# Back_Drill_Example.net
KiCad netlist of a schematic drawn in Altium Designer
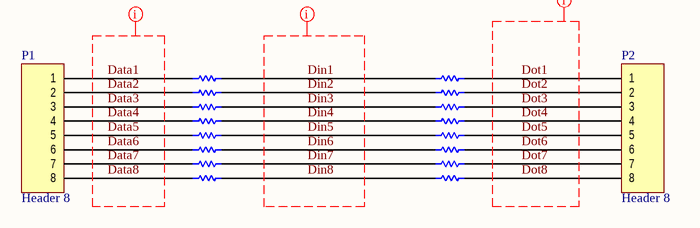
[diagram p0: Back Drill Example.SchDoc]

(export (version "E")
  (design (tool "Eeschema 10.0.6"))
  (components
    (comp (ref "P1")
      (value "Header 8")
      (footprint "HDR1X8")
      (description "Header, 8-Pin")
      (fields (field (name "PUBLISHER") "Altium Limited"))
      (libsource (lib "") (part "Header 8_1"))
    )
    (comp (ref "P2")
      (value "Header 8")
      (footprint "HDR1X8")
      (description "Header, 8-Pin")
      (fields (field (name "PUBLISHER") "Altium Limited"))
      (libsource (lib "Miscellaneous Connectors") (part "Header 8"))
    )
    (comp (ref "R1")
      (value "1K 0603")
      (footprint "0603_L")
      (fields
        (field (name "MANUFACTURER") "Panasonic Electronic Components")
        (field (name "MANUFACTURER PART NUMBER") "ERJ-3GEYJ102V")
        (field (name "TOLERANCE") "±5%")
      )
      (libsource (lib "WCTopping") (part "Res1K_0603"))
    )
    (comp (ref "R2")
      (value "1K 0603")
      (footprint "0603_L")
      (fields
        (field (name "MANUFACTURER") "Panasonic Electronic Components")
        (field (name "MANUFACTURER PART NUMBER") "ERJ-3GEYJ102V")
        (field (name "TOLERANCE") "±5%")
      )
      (libsource (lib "WCTopping") (part "Res1K_0603"))
    )
    (comp (ref "R3")
      (value "1K 0603")
      (footprint "0603_L")
      (fields
        (field (name "MANUFACTURER") "Panasonic Electronic Components")
        (field (name "MANUFACTURER PART NUMBER") "ERJ-3GEYJ102V")
        (field (name "TOLERANCE") "±5%")
      )
      (libsource (lib "WCTopping") (part "Res1K_0603"))
    )
    (comp (ref "R4")
      (value "1K 0603")
      (footprint "0603_L")
      (fields
        (field (name "MANUFACTURER") "Panasonic Electronic Components")
        (field (name "MANUFACTURER PART NUMBER") "ERJ-3GEYJ102V")
        (field (name "TOLERANCE") "±5%")
      )
      (libsource (lib "WCTopping") (part "Res1K_0603"))
    )
    (comp (ref "R5")
      (value "1K 0603")
      (footprint "0603_L")
      (fields
        (field (name "MANUFACTURER") "Panasonic Electronic Components")
        (field (name "MANUFACTURER PART NUMBER") "ERJ-3GEYJ102V")
        (field (name "TOLERANCE") "±5%")
      )
      (libsource (lib "WCTopping") (part "Res1K_0603"))
    )
    (comp (ref "R6")
      (value "1K 0603")
      (footprint "0603_L")
      (fields
        (field (name "MANUFACTURER") "Panasonic Electronic Components")
        (field (name "MANUFACTURER PART NUMBER") "ERJ-3GEYJ102V")
        (field (name "TOLERANCE") "±5%")
      )
      (libsource (lib "WCTopping") (part "Res1K_0603"))
    )
    (comp (ref "R7")
      (value "1K 0603")
      (footprint "0603_L")
      (fields
        (field (name "MANUFACTURER") "Panasonic Electronic Components")
        (field (name "MANUFACTURER PART NUMBER") "ERJ-3GEYJ102V")
        (field (name "TOLERANCE") "±5%")
      )
      (libsource (lib "WCTopping") (part "Res1K_0603"))
    )
    (comp (ref "R8")
      (value "1K 0603")
      (footprint "0603_L")
      (fields
        (field (name "MANUFACTURER") "Panasonic Electronic Components")
        (field (name "MANUFACTURER PART NUMBER") "ERJ-3GEYJ102V")
        (field (name "TOLERANCE") "±5%")
      )
      (libsource (lib "WCTopping") (part "Res1K_0603"))
    )
    (comp (ref "RS1")
      (value "1K 0603")
      (footprint "0603_L")
      (fields
        (field (name "MANUFACTURER") "Panasonic Electronic Components")
        (field (name "MANUFACTURER PART NUMBER") "ERJ-3GEYJ102V")
        (field (name "TOLERANCE") "±5%")
      )
      (libsource (lib "WCTopping") (part "Res1K_0603"))
    )
    (comp (ref "RS2")
      (value "1K 0603")
      (footprint "0603_L")
      (fields
        (field (name "MANUFACTURER") "Panasonic Electronic Components")
        (field (name "MANUFACTURER PART NUMBER") "ERJ-3GEYJ102V")
        (field (name "TOLERANCE") "±5%")
      )
      (libsource (lib "WCTopping") (part "Res1K_0603"))
    )
    (comp (ref "RS3")
      (value "1K 0603")
      (footprint "0603_L")
      (fields
        (field (name "MANUFACTURER") "Panasonic Electronic Components")
        (field (name "MANUFACTURER PART NUMBER") "ERJ-3GEYJ102V")
        (field (name "TOLERANCE") "±5%")
      )
      (libsource (lib "WCTopping") (part "Res1K_0603"))
    )
    (comp (ref "RS4")
      (value "1K 0603")
      (footprint "0603_L")
      (fields
        (field (name "MANUFACTURER") "Panasonic Electronic Components")
        (field (name "MANUFACTURER PART NUMBER") "ERJ-3GEYJ102V")
        (field (name "TOLERANCE") "±5%")
      )
      (libsource (lib "WCTopping") (part "Res1K_0603"))
    )
    (comp (ref "RS5")
      (value "1K 0603")
      (footprint "0603_L")
      (fields
        (field (name "MANUFACTURER") "Panasonic Electronic Components")
        (field (name "MANUFACTURER PART NUMBER") "ERJ-3GEYJ102V")
        (field (name "TOLERANCE") "±5%")
      )
      (libsource (lib "WCTopping") (part "Res1K_0603"))
    )
    (comp (ref "RS6")
      (value "1K 0603")
      (footprint "0603_L")
      (fields
        (field (name "MANUFACTURER") "Panasonic Electronic Components")
        (field (name "MANUFACTURER PART NUMBER") "ERJ-3GEYJ102V")
        (field (name "TOLERANCE") "±5%")
      )
      (libsource (lib "WCTopping") (part "Res1K_0603"))
    )
    (comp (ref "RS7")
      (value "1K 0603")
      (footprint "0603_L")
      (fields
        (field (name "MANUFACTURER") "Panasonic Electronic Components")
        (field (name "MANUFACTURER PART NUMBER") "ERJ-3GEYJ102V")
        (field (name "TOLERANCE") "±5%")
      )
      (libsource (lib "WCTopping") (part "Res1K_0603"))
    )
    (comp (ref "RS8")
      (value "1K 0603")
      (footprint "0603_L")
      (fields
        (field (name "MANUFACTURER") "Panasonic Electronic Components")
        (field (name "MANUFACTURER PART NUMBER") "ERJ-3GEYJ102V")
        (field (name "TOLERANCE") "±5%")
      )
      (libsource (lib "WCTopping") (part "Res1K_0603"))
    )
  )
  (nets
    (net (code "1") (name "/Data1") (class "Default")
      (node (ref "P1") (pin "1") (pinfunction "1_1") (pintype "passive"))
      (node (ref "R1") (pin "1") (pinfunction "1_1") (pintype "passive"))
    )
    (net (code "2") (name "/Data2") (class "Default")
      (node (ref "P1") (pin "2") (pinfunction "2_2") (pintype "passive"))
      (node (ref "R2") (pin "1") (pinfunction "1_1") (pintype "passive"))
    )
    (net (code "3") (name "/Data3") (class "Default")
      (node (ref "P1") (pin "3") (pinfunction "3_3") (pintype "passive"))
      (node (ref "R3") (pin "1") (pinfunction "1_1") (pintype "passive"))
    )
    (net (code "4") (name "/Data4") (class "Default")
      (node (ref "P1") (pin "4") (pinfunction "4_4") (pintype "passive"))
      (node (ref "R4") (pin "1") (pinfunction "1_1") (pintype "passive"))
    )
    (net (code "5") (name "/Data5") (class "Default")
      (node (ref "P1") (pin "5") (pinfunction "5_5") (pintype "passive"))
      (node (ref "R5") (pin "1") (pinfunction "1_1") (pintype "passive"))
    )
    (net (code "6") (name "/Data6") (class "Default")
      (node (ref "P1") (pin "6") (pinfunction "6_6") (pintype "passive"))
      (node (ref "R6") (pin "1") (pinfunction "1_1") (pintype "passive"))
    )
    (net (code "7") (name "/Data7") (class "Default")
      (node (ref "P1") (pin "7") (pinfunction "7_7") (pintype "passive"))
      (node (ref "R7") (pin "1") (pinfunction "1_1") (pintype "passive"))
    )
    (net (code "8") (name "/Data8") (class "Default")
      (node (ref "P1") (pin "8") (pinfunction "8_8") (pintype "passive"))
      (node (ref "R8") (pin "1") (pinfunction "1_1") (pintype "passive"))
    )
    (net (code "9") (name "/Din1") (class "Default")
      (node (ref "R1") (pin "2") (pinfunction "2_2") (pintype "passive"))
      (node (ref "RS1") (pin "1") (pinfunction "1_1") (pintype "passive"))
    )
    (net (code "10") (name "/Din2") (class "Default")
      (node (ref "R2") (pin "2") (pinfunction "2_2") (pintype "passive"))
      (node (ref "RS2") (pin "1") (pinfunction "1_1") (pintype "passive"))
    )
    (net (code "11") (name "/Din3") (class "Default")
      (node (ref "R3") (pin "2") (pinfunction "2_2") (pintype "passive"))
      (node (ref "RS3") (pin "1") (pinfunction "1_1") (pintype "passive"))
    )
    (net (code "12") (name "/Din4") (class "Default")
      (node (ref "R4") (pin "2") (pinfunction "2_2") (pintype "passive"))
      (node (ref "RS4") (pin "1") (pinfunction "1_1") (pintype "passive"))
    )
    (net (code "13") (name "/Din5") (class "Default")
      (node (ref "R5") (pin "2") (pinfunction "2_2") (pintype "passive"))
      (node (ref "RS5") (pin "1") (pinfunction "1_1") (pintype "passive"))
    )
    (net (code "14") (name "/Din6") (class "Default")
      (node (ref "R6") (pin "2") (pinfunction "2_2") (pintype "passive"))
      (node (ref "RS6") (pin "1") (pinfunction "1_1") (pintype "passive"))
    )
    (net (code "15") (name "/Din7") (class "Default")
      (node (ref "R7") (pin "2") (pinfunction "2_2") (pintype "passive"))
      (node (ref "RS7") (pin "1") (pinfunction "1_1") (pintype "passive"))
    )
    (net (code "16") (name "/Din8") (class "Default")
      (node (ref "R8") (pin "2") (pinfunction "2_2") (pintype "passive"))
      (node (ref "RS8") (pin "1") (pinfunction "1_1") (pintype "passive"))
    )
    (net (code "17") (name "/Dot1") (class "Default")
      (node (ref "P2") (pin "1") (pinfunction "1_1") (pintype "passive"))
      (node (ref "RS1") (pin "2") (pinfunction "2_2") (pintype "passive"))
    )
    (net (code "18") (name "/Dot2") (class "Default")
      (node (ref "P2") (pin "2") (pinfunction "2_2") (pintype "passive"))
      (node (ref "RS2") (pin "2") (pinfunction "2_2") (pintype "passive"))
    )
    (net (code "19") (name "/Dot3") (class "Default")
      (node (ref "P2") (pin "3") (pinfunction "3_3") (pintype "passive"))
      (node (ref "RS3") (pin "2") (pinfunction "2_2") (pintype "passive"))
    )
    (net (code "20") (name "/Dot4") (class "Default")
      (node (ref "P2") (pin "4") (pinfunction "4_4") (pintype "passive"))
      (node (ref "RS4") (pin "2") (pinfunction "2_2") (pintype "passive"))
    )
    (net (code "21") (name "/Dot5") (class "Default")
      (node (ref "P2") (pin "5") (pinfunction "5_5") (pintype "passive"))
      (node (ref "RS5") (pin "2") (pinfunction "2_2") (pintype "passive"))
    )
    (net (code "22") (name "/Dot6") (class "Default")
      (node (ref "P2") (pin "6") (pinfunction "6_6") (pintype "passive"))
      (node (ref "RS6") (pin "2") (pinfunction "2_2") (pintype "passive"))
    )
    (net (code "23") (name "/Dot7") (class "Default")
      (node (ref "P2") (pin "7") (pinfunction "7_7") (pintype "passive"))
      (node (ref "RS7") (pin "2") (pinfunction "2_2") (pintype "passive"))
    )
    (net (code "24") (name "/Dot8") (class "Default")
      (node (ref "P2") (pin "8") (pinfunction "8_8") (pintype "passive"))
      (node (ref "RS8") (pin "2") (pinfunction "2_2") (pintype "passive"))
    )
  )
)
